# vmuzero_keyonly.net
KiCad netlist of a schematic drawn in EAGLE
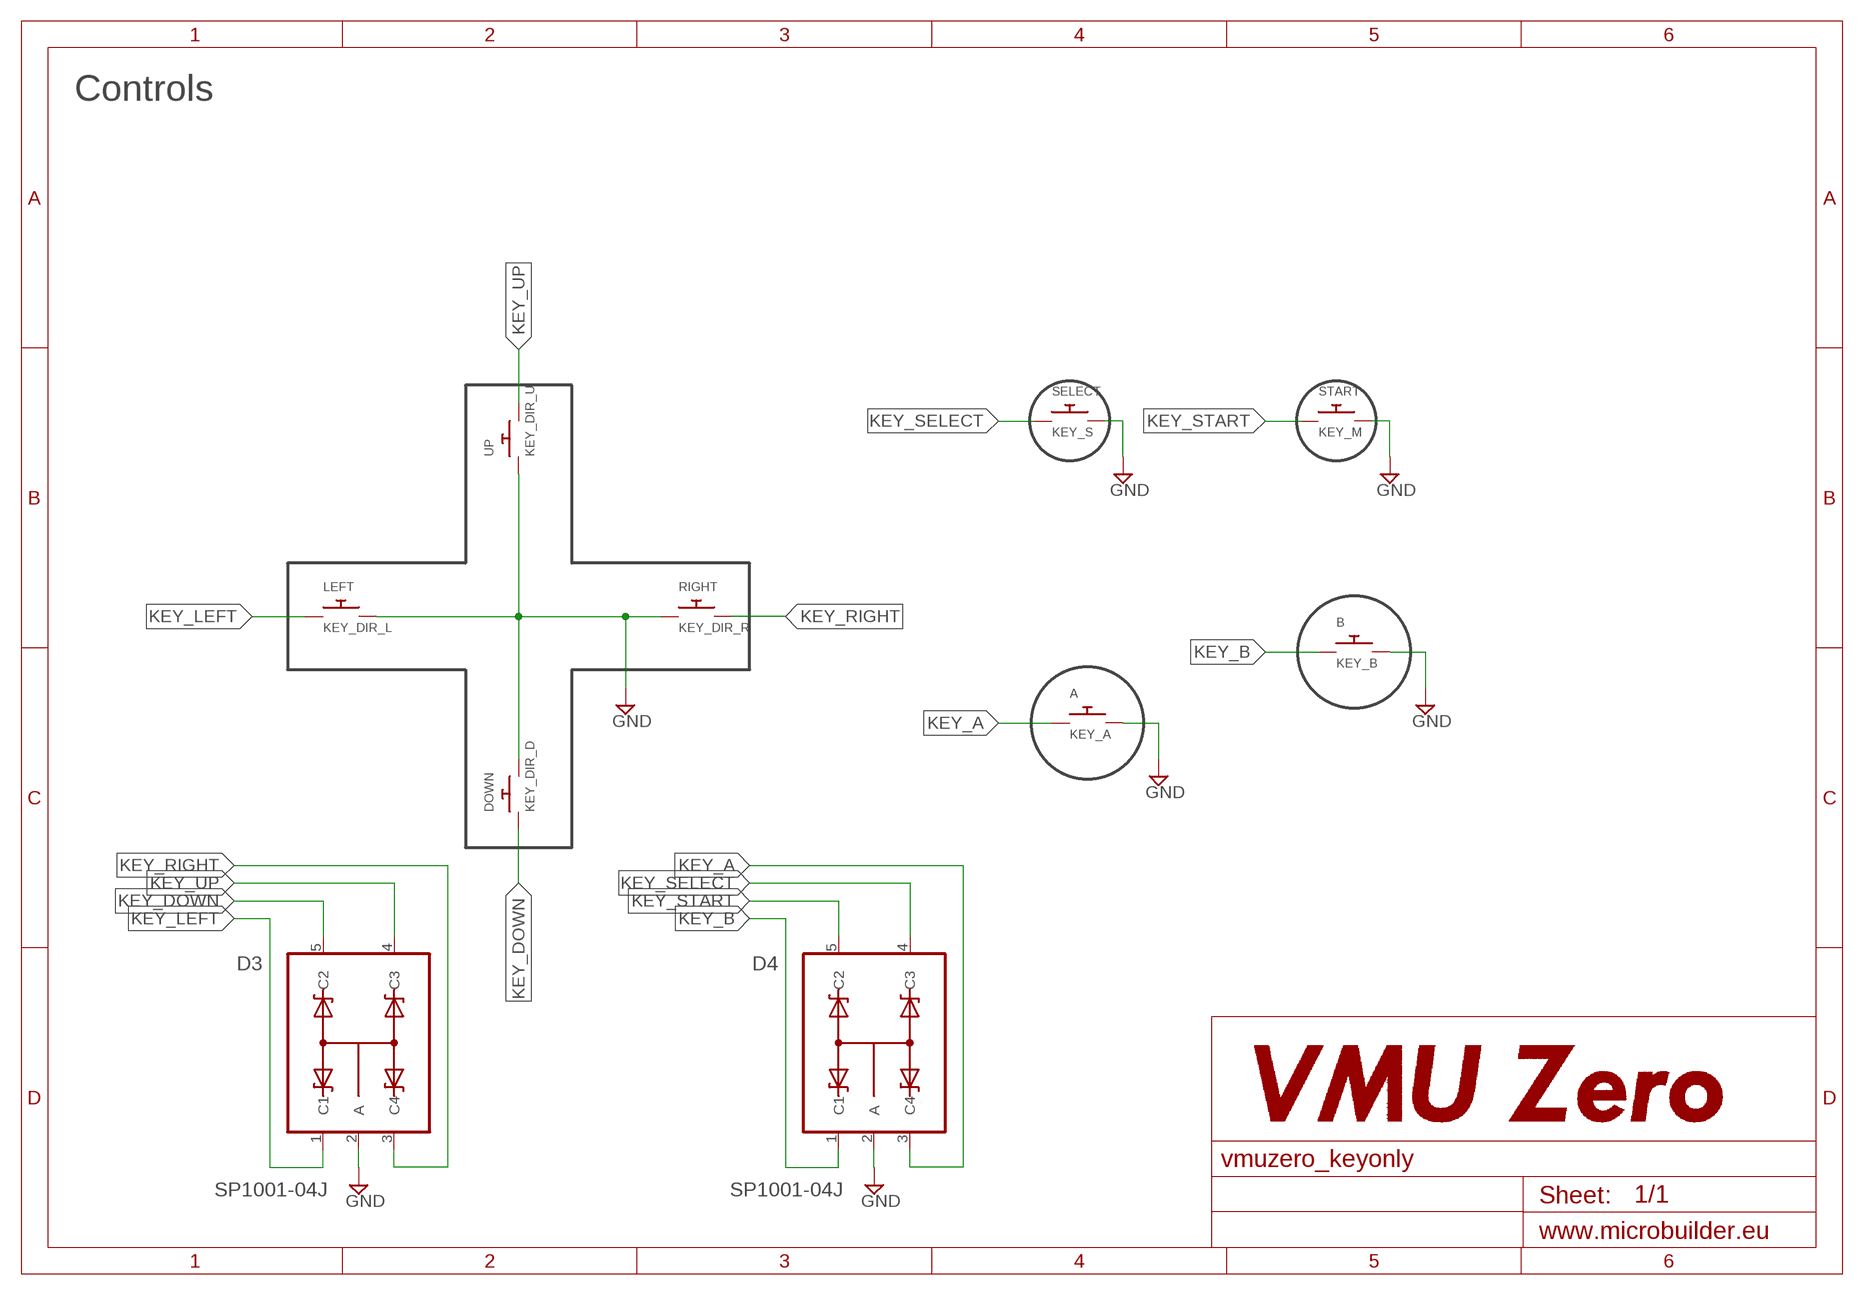
[diagram p0: schematic, sheet 1]

(export (version "E")
  (design (tool "Eeschema 10.0.6"))
  (components
    (comp (ref "A")
      (value "KEY_A")
      (footprint "eagle-import:KEYPAD_VMU_R26")
      (libsource (lib "eagle-import") (part "SWITCH_PUSH_VMU"))
    )
    (comp (ref "B")
      (value "KEY_B")
      (footprint "eagle-import:KEYPAD_VMU_R26")
      (libsource (lib "eagle-import") (part "SWITCH_PUSH_VMU"))
    )
    (comp (ref "D3")
      (value "SP1001-04J")
      (footprint "eagle-import:SC70-5")
      (fields (field (name "MPN") "SP1001-04"))
      (libsource (lib "eagle-import") (part "SP1001-04J"))
    )
    (comp (ref "D4")
      (value "SP1001-04J")
      (footprint "eagle-import:SC70-5")
      (fields (field (name "MPN") "SP1001-04"))
      (libsource (lib "eagle-import") (part "SP1001-04J"))
    )
    (comp (ref "DOWN")
      (value "KEY_DIR_D")
      (footprint "eagle-import:KEYPAD_VMU_R26")
      (libsource (lib "eagle-import") (part "SWITCH_PUSH_VMU"))
    )
    (comp (ref "LEFT")
      (value "KEY_DIR_L")
      (footprint "eagle-import:KEYPAD_VMU_R26")
      (libsource (lib "eagle-import") (part "SWITCH_PUSH_VMU"))
    )
    (comp (ref "RIGHT")
      (value "KEY_DIR_R")
      (footprint "eagle-import:KEYPAD_VMU_R26")
      (libsource (lib "eagle-import") (part "SWITCH_PUSH_VMU"))
    )
    (comp (ref "SELECT")
      (value "KEY_S")
      (footprint "eagle-import:KEYPAD_VMU_R26")
      (libsource (lib "eagle-import") (part "SWITCH_PUSH_VMU"))
    )
    (comp (ref "START")
      (value "KEY_M")
      (footprint "eagle-import:KEYPAD_VMU_R26")
      (libsource (lib "eagle-import") (part "SWITCH_PUSH_VMU"))
    )
    (comp (ref "UP")
      (value "KEY_DIR_U")
      (footprint "eagle-import:KEYPAD_VMU_R26")
      (libsource (lib "eagle-import") (part "SWITCH_PUSH_VMU"))
    )
  )
  (nets
    (net (code "1") (name "GND") (class "Default")
      (node (ref "A") (pin "2") (pinfunction "P$2_2") (pintype "passive"))
      (node (ref "B") (pin "2") (pinfunction "P$2_2") (pintype "passive"))
      (node (ref "D3") (pin "2") (pinfunction "A_2") (pintype "passive"))
      (node (ref "D4") (pin "2") (pinfunction "A_2") (pintype "passive"))
      (node (ref "DOWN") (pin "2") (pinfunction "P$2_2") (pintype "passive"))
      (node (ref "LEFT") (pin "2") (pinfunction "P$2_2") (pintype "passive"))
      (node (ref "RIGHT") (pin "1") (pinfunction "P$1_1") (pintype "passive"))
      (node (ref "SELECT") (pin "2") (pinfunction "P$2_2") (pintype "passive"))
      (node (ref "START") (pin "2") (pinfunction "P$2_2") (pintype "passive"))
      (node (ref "UP") (pin "1") (pinfunction "P$1_1") (pintype "passive"))
    )
    (net (code "2") (name "KEY_A") (class "Default")
      (node (ref "A") (pin "1") (pinfunction "P$1_1") (pintype "passive"))
      (node (ref "D4") (pin "3") (pinfunction "C4_3") (pintype "passive"))
    )
    (net (code "3") (name "KEY_B") (class "Default")
      (node (ref "B") (pin "1") (pinfunction "P$1_1") (pintype "passive"))
      (node (ref "D4") (pin "1") (pinfunction "C1_1") (pintype "passive"))
    )
    (net (code "4") (name "KEY_DOWN") (class "Default")
      (node (ref "D3") (pin "5") (pinfunction "C2_5") (pintype "passive"))
      (node (ref "DOWN") (pin "1") (pinfunction "P$1_1") (pintype "passive"))
    )
    (net (code "5") (name "KEY_LEFT") (class "Default")
      (node (ref "D3") (pin "1") (pinfunction "C1_1") (pintype "passive"))
      (node (ref "LEFT") (pin "1") (pinfunction "P$1_1") (pintype "passive"))
    )
    (net (code "6") (name "KEY_RIGHT") (class "Default")
      (node (ref "D3") (pin "3") (pinfunction "C4_3") (pintype "passive"))
      (node (ref "RIGHT") (pin "2") (pinfunction "P$2_2") (pintype "passive"))
    )
    (net (code "7") (name "KEY_SELECT") (class "Default")
      (node (ref "D4") (pin "4") (pinfunction "C3_4") (pintype "passive"))
      (node (ref "SELECT") (pin "1") (pinfunction "P$1_1") (pintype "passive"))
    )
    (net (code "8") (name "KEY_START") (class "Default")
      (node (ref "D4") (pin "5") (pinfunction "C2_5") (pintype "passive"))
      (node (ref "START") (pin "1") (pinfunction "P$1_1") (pintype "passive"))
    )
    (net (code "9") (name "KEY_UP") (class "Default")
      (node (ref "D3") (pin "4") (pinfunction "C3_4") (pintype "passive"))
      (node (ref "UP") (pin "2") (pinfunction "P$2_2") (pintype "passive"))
    )
  )
)
